# BOTTOM_pcb_redonda_definitiva.net
KiCad netlist of a schematic drawn in EAGLE
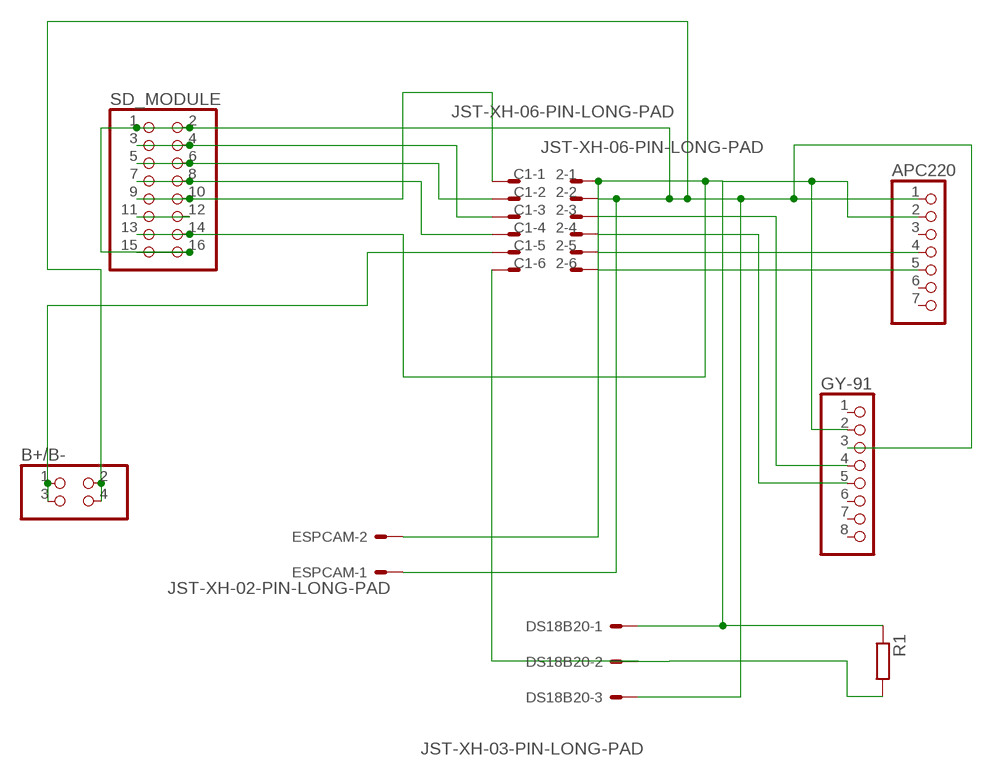
[diagram p0: schematic, sheet 1]

(export (version "E")
  (design (tool "Eeschema 10.0.6"))
  (components
    (comp (ref "2")
      (value "JST-XH-06-PIN-LONG-PAD")
      (footprint "eagle-import:JST-XH-06-PACKAGE-LONG-PAD")
      (libsource (lib "eagle-import") (part "JST-XH-06-PIN-LONG-PAD"))
    )
    (comp (ref "APC220")
      (value "PINHD-1X7")
      (footprint "eagle-import:1X07")
      (libsource (lib "eagle-import") (part "PINHD-1X7"))
    )
    (comp (ref "B+/B-")
      (value "PINHD-2X2")
      (footprint "eagle-import:2X02")
      (libsource (lib "eagle-import") (part "PINHD-2X2"))
    )
    (comp (ref "C1")
      (value "JST-XH-06-PIN-LONG-PAD")
      (footprint "eagle-import:JST-XH-06-PACKAGE-LONG-PAD")
      (libsource (lib "eagle-import") (part "JST-XH-06-PIN-LONG-PAD"))
    )
    (comp (ref "DS18B20")
      (value "JST-XH-03-PIN-LONG-PAD")
      (footprint "eagle-import:JST-XH-03-PACKAGE-LONG-PAD")
      (libsource (lib "eagle-import") (part "JST-XH-03-PIN-LONG-PAD"))
    )
    (comp (ref "ESPCAM")
      (value "JST-XH-02-PIN-LONG-PAD")
      (footprint "eagle-import:JST-XH-02-PACKAGE-LONG-PAD")
      (libsource (lib "eagle-import") (part "JST-XH-02-PIN-LONG-PAD"))
    )
    (comp (ref "GY-91")
      (value "PINHD-1X8")
      (footprint "eagle-import:1X08")
      (libsource (lib "eagle-import") (part "PINHD-1X8"))
    )
    (comp (ref "R1")
      (value "R-EU_0207/10")
      (footprint "eagle-import:0207_10")
      (libsource (lib "eagle-import") (part "R-EU_0207/10"))
    )
    (comp (ref "SD_MODULE")
      (value "PINHD-2X8")
      (footprint "eagle-import:2X08")
      (libsource (lib "eagle-import") (part "PINHD-2X8"))
    )
  )
  (nets
    (net (code "1") (name "Net-(2A-S)") (class "Default")
      (node (ref "2") (pin "1") (pinfunction "S_1") (pintype "passive"))
      (node (ref "APC220") (pin "2") (pinfunction "2_2") (pintype "passive"))
      (node (ref "DS18B20") (pin "1") (pinfunction "S_1") (pintype "passive"))
      (node (ref "ESPCAM") (pin "2") (pinfunction "S_2") (pintype "passive"))
      (node (ref "GY-91") (pin "2") (pinfunction "2_2") (pintype "passive"))
      (node (ref "R1") (pin "1") (pinfunction "1_1") (pintype "passive"))
      (node (ref "SD_MODULE") (pin "13") (pinfunction "13_13") (pintype "passive"))
      (node (ref "SD_MODULE") (pin "14") (pinfunction "14_14") (pintype "passive"))
    )
    (net (code "2") (name "Net-(2B-S)") (class "Default")
      (node (ref "2") (pin "2") (pinfunction "S_2") (pintype "passive"))
      (node (ref "APC220") (pin "1") (pinfunction "1_1") (pintype "passive"))
      (node (ref "B+/B-") (pin "2") (pinfunction "2_2") (pintype "passive"))
      (node (ref "B+/B-") (pin "4") (pinfunction "4_4") (pintype "passive"))
      (node (ref "DS18B20") (pin "3") (pinfunction "S_3") (pintype "passive"))
      (node (ref "ESPCAM") (pin "1") (pinfunction "S_1") (pintype "passive"))
      (node (ref "GY-91") (pin "3") (pinfunction "3_3") (pintype "passive"))
      (node (ref "SD_MODULE") (pin "1") (pinfunction "1_1") (pintype "passive"))
      (node (ref "SD_MODULE") (pin "15") (pinfunction "15_15") (pintype "passive"))
      (node (ref "SD_MODULE") (pin "16") (pinfunction "16_16") (pintype "passive"))
      (node (ref "SD_MODULE") (pin "2") (pinfunction "2_2") (pintype "passive"))
    )
    (net (code "3") (name "Net-(2C-S)") (class "Default")
      (node (ref "2") (pin "3") (pinfunction "S_3") (pintype "passive"))
      (node (ref "GY-91") (pin "4") (pinfunction "4_4") (pintype "passive"))
    )
    (net (code "4") (name "Net-(2D-S)") (class "Default")
      (node (ref "2") (pin "4") (pinfunction "S_4") (pintype "passive"))
      (node (ref "GY-91") (pin "5") (pinfunction "5_5") (pintype "passive"))
    )
    (net (code "5") (name "Net-(2E-S)") (class "Default")
      (node (ref "2") (pin "5") (pinfunction "S_5") (pintype "passive"))
      (node (ref "APC220") (pin "4") (pinfunction "4_4") (pintype "passive"))
    )
    (net (code "6") (name "Net-(2F-S)") (class "Default")
      (node (ref "2") (pin "6") (pinfunction "S_6") (pintype "passive"))
      (node (ref "APC220") (pin "5") (pinfunction "5_5") (pintype "passive"))
    )
    (net (code "7") (name "Net-(C1A-S)") (class "Default")
      (node (ref "C1") (pin "1") (pinfunction "S_1") (pintype "passive"))
      (node (ref "SD_MODULE") (pin "10") (pinfunction "10_10") (pintype "passive"))
      (node (ref "SD_MODULE") (pin "9") (pinfunction "9_9") (pintype "passive"))
    )
    (net (code "8") (name "Net-(C1B-S)") (class "Default")
      (node (ref "C1") (pin "2") (pinfunction "S_2") (pintype "passive"))
      (node (ref "SD_MODULE") (pin "5") (pinfunction "5_5") (pintype "passive"))
      (node (ref "SD_MODULE") (pin "6") (pinfunction "6_6") (pintype "passive"))
    )
    (net (code "9") (name "Net-(C1C-S)") (class "Default")
      (node (ref "C1") (pin "3") (pinfunction "S_3") (pintype "passive"))
      (node (ref "SD_MODULE") (pin "3") (pinfunction "3_3") (pintype "passive"))
      (node (ref "SD_MODULE") (pin "4") (pinfunction "4_4") (pintype "passive"))
    )
    (net (code "10") (name "Net-(C1D-S)") (class "Default")
      (node (ref "C1") (pin "4") (pinfunction "S_4") (pintype "passive"))
      (node (ref "SD_MODULE") (pin "7") (pinfunction "7_7") (pintype "passive"))
      (node (ref "SD_MODULE") (pin "8") (pinfunction "8_8") (pintype "passive"))
    )
    (net (code "11") (name "Net-(C1E-S)") (class "Default")
      (node (ref "B+/B-") (pin "1") (pinfunction "1_1") (pintype "passive"))
      (node (ref "B+/B-") (pin "3") (pinfunction "3_3") (pintype "passive"))
      (node (ref "C1") (pin "5") (pinfunction "S_5") (pintype "passive"))
    )
    (net (code "12") (name "Net-(C1F-S)") (class "Default")
      (node (ref "C1") (pin "6") (pinfunction "S_6") (pintype "passive"))
      (node (ref "DS18B20") (pin "2") (pinfunction "S_2") (pintype "passive"))
      (node (ref "R1") (pin "2") (pinfunction "2_2") (pintype "passive"))
    )
    (net (code "13") (name "Net-(SD_MODULE-Pad11)") (class "Default")
      (node (ref "SD_MODULE") (pin "11") (pinfunction "11_11") (pintype "passive"))
      (node (ref "SD_MODULE") (pin "12") (pinfunction "12_12") (pintype "passive"))
    )
    (net (code "14") (name "unconnected-(APC220-Pad3)") (class "Default")
      (node (ref "APC220") (pin "3") (pinfunction "3_3") (pintype "passive"))
    )
    (net (code "15") (name "unconnected-(APC220-Pad6)") (class "Default")
      (node (ref "APC220") (pin "6") (pinfunction "6_6") (pintype "passive"))
    )
    (net (code "16") (name "unconnected-(APC220-Pad7)") (class "Default")
      (node (ref "APC220") (pin "7") (pinfunction "7_7") (pintype "passive"))
    )
    (net (code "17") (name "unconnected-(GY-91-Pad1)") (class "Default")
      (node (ref "GY-91") (pin "1") (pinfunction "1_1") (pintype "passive"))
    )
    (net (code "18") (name "unconnected-(GY-91-Pad6)") (class "Default")
      (node (ref "GY-91") (pin "6") (pinfunction "6_6") (pintype "passive"))
    )
    (net (code "19") (name "unconnected-(GY-91-Pad7)") (class "Default")
      (node (ref "GY-91") (pin "7") (pinfunction "7_7") (pintype "passive"))
    )
    (net (code "20") (name "unconnected-(GY-91-Pad8)") (class "Default")
      (node (ref "GY-91") (pin "8") (pinfunction "8_8") (pintype "passive"))
    )
  )
)
